# gemini.net
KiCad netlist of a schematic drawn in EAGLE
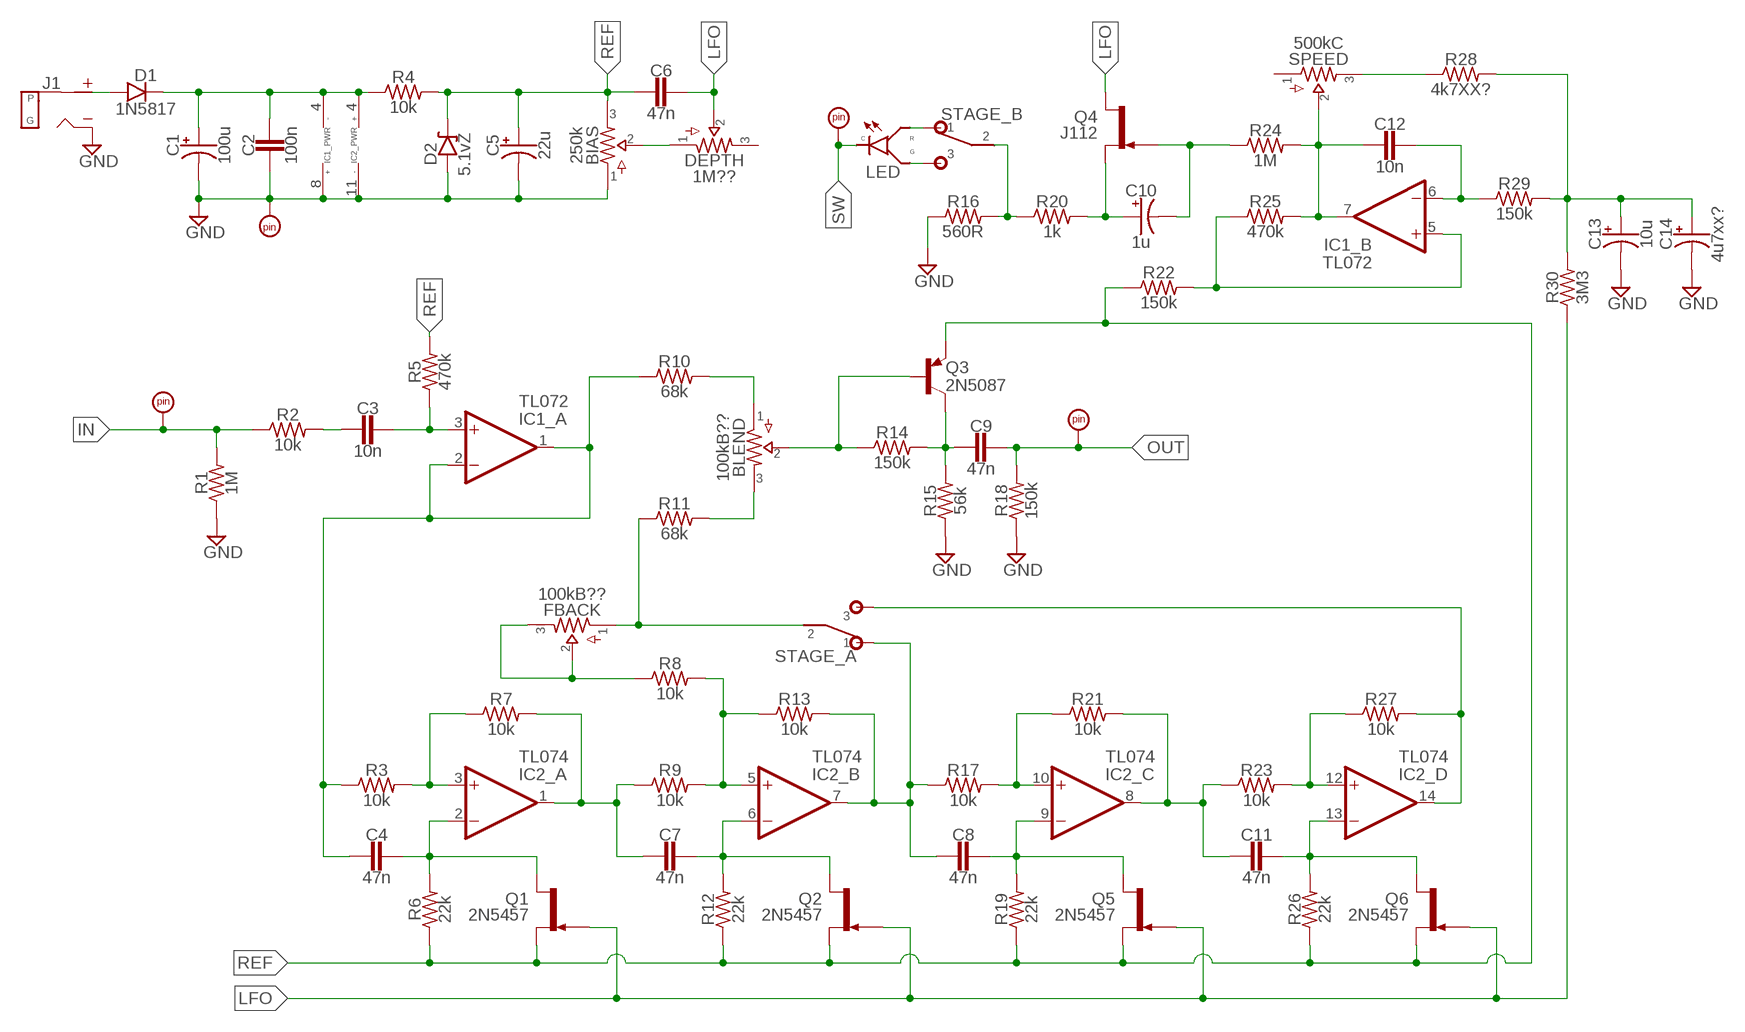
[diagram p0: schematic, sheet 1]

(export (version "E")
  (design (tool "Eeschema 10.0.6"))
  (components
    (comp (ref "BIAS")
      (value "250k")
      (footprint "eagle-import:2262_TRIM")
      (libsource (lib "eagle-import") (part "POTSTRIM"))
    )
    (comp (ref "BLEND")
      (value "100kB??")
      (footprint "eagle-import:16MM")
      (libsource (lib "eagle-import") (part "POTS16MM"))
    )
    (comp (ref "C1")
      (value "100u")
      (footprint "eagle-import:050_020_1")
      (libsource (lib "eagle-import") (part "0501"))
    )
    (comp (ref "C2")
      (value "100n")
      (footprint "eagle-import:050X030_025_2")
      (libsource (lib "eagle-import") (part "CER/FILM2"))
    )
    (comp (ref "C3")
      (value "10n")
      (footprint "eagle-import:050X030_025_2")
      (libsource (lib "eagle-import") (part "CER/FILM2"))
    )
    (comp (ref "C4")
      (value "47n")
      (footprint "eagle-import:050X030_025_2")
      (libsource (lib "eagle-import") (part "CER/FILM2"))
    )
    (comp (ref "C5")
      (value "22u")
      (footprint "eagle-import:050_020_1")
      (libsource (lib "eagle-import") (part "0501"))
    )
    (comp (ref "C6")
      (value "47n")
      (footprint "eagle-import:050X030_025_2")
      (libsource (lib "eagle-import") (part "CER/FILM2"))
    )
    (comp (ref "C7")
      (value "47n")
      (footprint "eagle-import:050X030_025_2")
      (libsource (lib "eagle-import") (part "CER/FILM2"))
    )
    (comp (ref "C8")
      (value "47n")
      (footprint "eagle-import:050X030_025_2")
      (libsource (lib "eagle-import") (part "CER/FILM2"))
    )
    (comp (ref "C9")
      (value "47n")
      (footprint "eagle-import:050X030_025_2")
      (libsource (lib "eagle-import") (part "CER/FILM2"))
    )
    (comp (ref "C10")
      (value "1u")
      (footprint "eagle-import:050_020_1")
      (libsource (lib "eagle-import") (part "0501"))
    )
    (comp (ref "C11")
      (value "47n")
      (footprint "eagle-import:050X030_025_2")
      (libsource (lib "eagle-import") (part "CER/FILM2"))
    )
    (comp (ref "C12")
      (value "10n")
      (footprint "eagle-import:050X030_025_2")
      (libsource (lib "eagle-import") (part "CER/FILM2"))
    )
    (comp (ref "C13")
      (value "10u")
      (footprint "eagle-import:050_020_1")
      (libsource (lib "eagle-import") (part "0501"))
    )
    (comp (ref "C14")
      (value "4u7xx?")
      (footprint "eagle-import:050_020_1")
      (libsource (lib "eagle-import") (part "0501"))
    )
    (comp (ref "D1")
      (value "1N5817")
      (footprint "eagle-import:DO41-2")
      (libsource (lib "eagle-import") (part "DO41.2"))
    )
    (comp (ref "D2")
      (value "5.1vZ")
      (footprint "eagle-import:DO41-3")
      (libsource (lib "eagle-import") (part "ZENER.3"))
    )
    (comp (ref "DEPTH")
      (value "1M??")
      (footprint "eagle-import:16MM")
      (libsource (lib "eagle-import") (part "POTS16MM"))
    )
    (comp (ref "FBACK")
      (value "100kB??")
      (footprint "eagle-import:16MM")
      (libsource (lib "eagle-import") (part "POTS16MM"))
    )
    (comp (ref "IC1")
      (value "TL072")
      (footprint "eagle-import:DIL08")
      (libsource (lib "eagle-import") (part "DUALTH"))
    )
    (comp (ref "IC2")
      (value "TL074")
      (footprint "eagle-import:DIL14")
      (libsource (lib "eagle-import") (part "QUADTH"))
    )
    (comp (ref "J1")
      (value "DC_MONO")
      (footprint "eagle-import:DC")
      (libsource (lib "eagle-import") (part "DC_MONO"))
    )
    (comp (ref "LED")
      (value "LED_DUAL")
      (footprint "eagle-import:LED_DUAL")
      (libsource (lib "eagle-import") (part "LED_DUAL"))
    )
    (comp (ref "PAD1")
      (value "PADSQR")
      (footprint "eagle-import:SQUARE")
      (libsource (lib "eagle-import") (part "PADSQR"))
    )
    (comp (ref "PAD2")
      (value "PADRND")
      (footprint "eagle-import:ROUND")
      (libsource (lib "eagle-import") (part "PADRND"))
    )
    (comp (ref "PAD3")
      (value "PADRND")
      (footprint "eagle-import:ROUND")
      (libsource (lib "eagle-import") (part "PADRND"))
    )
    (comp (ref "PAD4")
      (value "PADSQR")
      (footprint "eagle-import:SQUARE")
      (libsource (lib "eagle-import") (part "PADSQR"))
    )
    (comp (ref "Q1")
      (value "2N5457")
      (footprint "eagle-import:TO92-")
      (libsource (lib "eagle-import") (part "2N5457"))
    )
    (comp (ref "Q2")
      (value "2N5457")
      (footprint "eagle-import:TO92-")
      (libsource (lib "eagle-import") (part "2N5457"))
    )
    (comp (ref "Q3")
      (value "2N5087")
      (footprint "eagle-import:TO92-")
      (libsource (lib "eagle-import") (part "2N5087.1"))
    )
    (comp (ref "Q4")
      (value "J112")
      (footprint "eagle-import:TO92-")
      (libsource (lib "eagle-import") (part "J201"))
    )
    (comp (ref "Q5")
      (value "2N5457")
      (footprint "eagle-import:TO92-")
      (libsource (lib "eagle-import") (part "2N5457"))
    )
    (comp (ref "Q6")
      (value "2N5457")
      (footprint "eagle-import:TO92-")
      (libsource (lib "eagle-import") (part "2N5457"))
    )
    (comp (ref "R1")
      (value "1M")
      (footprint "eagle-import:R0207_3")
      (libsource (lib "eagle-import") (part "R_.3B"))
    )
    (comp (ref "R2")
      (value "10k")
      (footprint "eagle-import:R0207_3")
      (libsource (lib "eagle-import") (part "R_.3B"))
    )
    (comp (ref "R3")
      (value "10k")
      (footprint "eagle-import:R0207_3")
      (libsource (lib "eagle-import") (part "R_.3B"))
    )
    (comp (ref "R4")
      (value "10k")
      (footprint "eagle-import:R0207_3")
      (libsource (lib "eagle-import") (part "R_.3B"))
    )
    (comp (ref "R5")
      (value "470k")
      (footprint "eagle-import:R0207_3")
      (libsource (lib "eagle-import") (part "R_.3B"))
    )
    (comp (ref "R6")
      (value "22k")
      (footprint "eagle-import:R0207_3")
      (libsource (lib "eagle-import") (part "R_.3B"))
    )
    (comp (ref "R7")
      (value "10k")
      (footprint "eagle-import:R0207_3")
      (libsource (lib "eagle-import") (part "R_.3B"))
    )
    (comp (ref "R8")
      (value "10k")
      (footprint "eagle-import:R0207_3")
      (libsource (lib "eagle-import") (part "R_.3B"))
    )
    (comp (ref "R9")
      (value "10k")
      (footprint "eagle-import:R0207_3")
      (libsource (lib "eagle-import") (part "R_.3B"))
    )
    (comp (ref "R10")
      (value "68k")
      (footprint "eagle-import:R0207_3")
      (libsource (lib "eagle-import") (part "R_.3B"))
    )
    (comp (ref "R11")
      (value "68k")
      (footprint "eagle-import:R0207_3")
      (libsource (lib "eagle-import") (part "R_.3B"))
    )
    (comp (ref "R12")
      (value "22k")
      (footprint "eagle-import:R0207_3")
      (libsource (lib "eagle-import") (part "R_.3B"))
    )
    (comp (ref "R13")
      (value "10k")
      (footprint "eagle-import:R0207_3")
      (libsource (lib "eagle-import") (part "R_.3B"))
    )
    (comp (ref "R14")
      (value "150k")
      (footprint "eagle-import:R0207_3")
      (libsource (lib "eagle-import") (part "R_.3B"))
    )
    (comp (ref "R15")
      (value "56k")
      (footprint "eagle-import:R0207_3")
      (libsource (lib "eagle-import") (part "R_.3B"))
    )
    (comp (ref "R16")
      (value "560R")
      (footprint "eagle-import:R0207_3")
      (libsource (lib "eagle-import") (part "R_.3B"))
    )
    (comp (ref "R17")
      (value "10k")
      (footprint "eagle-import:R0207_3")
      (libsource (lib "eagle-import") (part "R_.3B"))
    )
    (comp (ref "R18")
      (value "150k")
      (footprint "eagle-import:R0207_3")
      (libsource (lib "eagle-import") (part "R_.3B"))
    )
    (comp (ref "R19")
      (value "22k")
      (footprint "eagle-import:R0207_3")
      (libsource (lib "eagle-import") (part "R_.3B"))
    )
    (comp (ref "R20")
      (value "1k")
      (footprint "eagle-import:R0207_3")
      (libsource (lib "eagle-import") (part "R_.3B"))
    )
    (comp (ref "R21")
      (value "10k")
      (footprint "eagle-import:R0207_3")
      (libsource (lib "eagle-import") (part "R_.3B"))
    )
    (comp (ref "R22")
      (value "150k")
      (footprint "eagle-import:R0207_3")
      (libsource (lib "eagle-import") (part "R_.3B"))
    )
    (comp (ref "R23")
      (value "10k")
      (footprint "eagle-import:R0207_3")
      (libsource (lib "eagle-import") (part "R_.3B"))
    )
    (comp (ref "R24")
      (value "1M")
      (footprint "eagle-import:R0207_3")
      (libsource (lib "eagle-import") (part "R_.3B"))
    )
    (comp (ref "R25")
      (value "470k")
      (footprint "eagle-import:R0207_3")
      (libsource (lib "eagle-import") (part "R_.3B"))
    )
    (comp (ref "R26")
      (value "22k")
      (footprint "eagle-import:R0207_3")
      (libsource (lib "eagle-import") (part "R_.3B"))
    )
    (comp (ref "R27")
      (value "10k")
      (footprint "eagle-import:R0207_3")
      (libsource (lib "eagle-import") (part "R_.3B"))
    )
    (comp (ref "R28")
      (value "4k7XX?")
      (footprint "eagle-import:R0207_3")
      (libsource (lib "eagle-import") (part "R_.3B"))
    )
    (comp (ref "R29")
      (value "150k")
      (footprint "eagle-import:R0207_3")
      (libsource (lib "eagle-import") (part "R_.3B"))
    )
    (comp (ref "R30")
      (value "3M3")
      (footprint "eagle-import:R0207_3")
      (libsource (lib "eagle-import") (part "R_.3B"))
    )
    (comp (ref "SPEED")
      (value "500kC")
      (footprint "eagle-import:16MM")
      (libsource (lib "eagle-import") (part "POTS16MM"))
    )
    (comp (ref "STAGE")
      (value "DPDTPCB")
      (footprint "eagle-import:DPDT2_PCB")
      (libsource (lib "eagle-import") (part "DPDTPCB"))
    )
  )
  (nets
    (net (code "1") (name "GND") (class "Default")
      (node (ref "BIAS") (pin "1") (pinfunction "1_1") (pintype "passive"))
      (node (ref "C1") (pin "-") (pinfunction "-_-") (pintype "passive"))
      (node (ref "C13") (pin "-") (pinfunction "-_-") (pintype "passive"))
      (node (ref "C14") (pin "-") (pinfunction "-_-") (pintype "passive"))
      (node (ref "C2") (pin "2") (pinfunction "2_2") (pintype "passive"))
      (node (ref "C5") (pin "-") (pinfunction "-_-") (pintype "passive"))
      (node (ref "D2") (pin "A") (pinfunction "A_A") (pintype "passive"))
      (node (ref "IC1") (pin "8") (pinfunction "V+_8") (pintype "power_in"))
      (node (ref "IC2") (pin "11") (pinfunction "V-_11") (pintype "power_in"))
      (node (ref "J1") (pin "S") (pinfunction "SLEEVE_S") (pintype "passive"))
      (node (ref "PAD2") (pin "1") (pinfunction "P$1_1") (pintype "bidirectional"))
      (node (ref "R1") (pin "1") (pinfunction "1_1") (pintype "passive"))
      (node (ref "R15") (pin "1") (pinfunction "1_1") (pintype "passive"))
      (node (ref "R16") (pin "1") (pinfunction "1_1") (pintype "passive"))
      (node (ref "R18") (pin "1") (pinfunction "1_1") (pintype "passive"))
    )
    (net (code "2") (name "IN") (class "Default")
      (node (ref "PAD1") (pin "1") (pinfunction "P$1_1") (pintype "bidirectional"))
      (node (ref "R1") (pin "2") (pinfunction "2_2") (pintype "passive"))
      (node (ref "R2") (pin "1") (pinfunction "1_1") (pintype "passive"))
    )
    (net (code "3") (name "LFO") (class "Default")
      (node (ref "C6") (pin "1") (pinfunction "1_1") (pintype "passive"))
      (node (ref "DEPTH") (pin "2") (pinfunction "2_2") (pintype "passive"))
      (node (ref "Q1") (pin "1") (pinfunction "G_1") (pintype "passive"))
      (node (ref "Q2") (pin "1") (pinfunction "G_1") (pintype "passive"))
      (node (ref "Q4") (pin "3") (pinfunction "D_3") (pintype "passive"))
      (node (ref "Q5") (pin "1") (pinfunction "G_1") (pintype "passive"))
      (node (ref "Q6") (pin "1") (pinfunction "G_1") (pintype "passive"))
      (node (ref "R30") (pin "1") (pinfunction "1_1") (pintype "passive"))
    )
    (net (code "4") (name "Net-(BIAS-Pad2)") (class "Default")
      (node (ref "BIAS") (pin "2") (pinfunction "2_2") (pintype "passive"))
      (node (ref "DEPTH") (pin "1") (pinfunction "1_1") (pintype "passive"))
    )
    (net (code "5") (name "Net-(BLEND-Pad1)") (class "Default")
      (node (ref "BLEND") (pin "1") (pinfunction "1_1") (pintype "passive"))
      (node (ref "R10") (pin "2") (pinfunction "2_2") (pintype "passive"))
    )
    (net (code "6") (name "Net-(BLEND-Pad3)") (class "Default")
      (node (ref "BLEND") (pin "3") (pinfunction "3_3") (pintype "passive"))
      (node (ref "R11") (pin "2") (pinfunction "2_2") (pintype "passive"))
    )
    (net (code "7") (name "Net-(C3-Pad2)") (class "Default")
      (node (ref "C3") (pin "2") (pinfunction "2_2") (pintype "passive"))
      (node (ref "R2") (pin "2") (pinfunction "2_2") (pintype "passive"))
    )
    (net (code "8") (name "Net-(C13-Pad+)") (class "Default")
      (node (ref "C13") (pin "+") (pinfunction "+_+") (pintype "passive"))
      (node (ref "C14") (pin "+") (pinfunction "+_+") (pintype "passive"))
      (node (ref "R28") (pin "2") (pinfunction "2_2") (pintype "passive"))
      (node (ref "R29") (pin "2") (pinfunction "2_2") (pintype "passive"))
      (node (ref "R30") (pin "2") (pinfunction "2_2") (pintype "passive"))
    )
    (net (code "9") (name "Net-(FBACK-Pad2)") (class "Default")
      (node (ref "FBACK") (pin "2") (pinfunction "2_2") (pintype "passive"))
      (node (ref "FBACK") (pin "3") (pinfunction "3_3") (pintype "passive"))
      (node (ref "R8") (pin "1") (pinfunction "1_1") (pintype "passive"))
    )
    (net (code "10") (name "Net-(IC1A-+IN)") (class "Default")
      (node (ref "C3") (pin "1") (pinfunction "1_1") (pintype "passive"))
      (node (ref "IC1") (pin "3") (pinfunction "+IN_3") (pintype "input"))
      (node (ref "R5") (pin "1") (pinfunction "1_1") (pintype "passive"))
    )
    (net (code "11") (name "Net-(IC1A--IN)") (class "Default")
      (node (ref "C4") (pin "2") (pinfunction "2_2") (pintype "passive"))
      (node (ref "IC1") (pin "1") (pinfunction "OUT_1") (pintype "output"))
      (node (ref "IC1") (pin "2") (pinfunction "-IN_2") (pintype "input"))
      (node (ref "R10") (pin "1") (pinfunction "1_1") (pintype "passive"))
      (node (ref "R3") (pin "1") (pinfunction "1_1") (pintype "passive"))
    )
    (net (code "12") (name "Net-(IC1B-+IN)") (class "Default")
      (node (ref "IC1") (pin "5") (pinfunction "+IN_5") (pintype "input"))
      (node (ref "R22") (pin "2") (pinfunction "2_2") (pintype "passive"))
      (node (ref "R25") (pin "1") (pinfunction "1_1") (pintype "passive"))
    )
    (net (code "13") (name "Net-(IC1B--IN)") (class "Default")
      (node (ref "C12") (pin "1") (pinfunction "1_1") (pintype "passive"))
      (node (ref "IC1") (pin "6") (pinfunction "-IN_6") (pintype "input"))
      (node (ref "R29") (pin "1") (pinfunction "1_1") (pintype "passive"))
    )
    (net (code "14") (name "Net-(IC1B-OUT)") (class "Default")
      (node (ref "C12") (pin "2") (pinfunction "2_2") (pintype "passive"))
      (node (ref "IC1") (pin "7") (pinfunction "OUT_7") (pintype "output"))
      (node (ref "R24") (pin "2") (pinfunction "2_2") (pintype "passive"))
      (node (ref "R25") (pin "2") (pinfunction "2_2") (pintype "passive"))
      (node (ref "SPEED") (pin "2") (pinfunction "2_2") (pintype "passive"))
    )
    (net (code "15") (name "Net-(IC1C-V-)") (class "Default")
      (node (ref "C1") (pin "+") (pinfunction "+_+") (pintype "passive"))
      (node (ref "C2") (pin "1") (pinfunction "1_1") (pintype "passive"))
      (node (ref "D1") (pin "C") (pinfunction "C_C") (pintype "passive"))
      (node (ref "IC1") (pin "4") (pinfunction "V-_4") (pintype "power_in"))
      (node (ref "IC2") (pin "4") (pinfunction "V+_4") (pintype "power_in"))
      (node (ref "R4") (pin "1") (pinfunction "1_1") (pintype "passive"))
    )
    (net (code "16") (name "Net-(IC2A-+IN)") (class "Default")
      (node (ref "IC2") (pin "3") (pinfunction "+IN_3") (pintype "input"))
      (node (ref "R3") (pin "2") (pinfunction "2_2") (pintype "passive"))
      (node (ref "R7") (pin "1") (pinfunction "1_1") (pintype "passive"))
    )
    (net (code "17") (name "Net-(IC2A--IN)") (class "Default")
      (node (ref "C4") (pin "1") (pinfunction "1_1") (pintype "passive"))
      (node (ref "IC2") (pin "2") (pinfunction "-IN_2") (pintype "input"))
      (node (ref "Q1") (pin "3") (pinfunction "D_3") (pintype "passive"))
      (node (ref "R6") (pin "2") (pinfunction "2_2") (pintype "passive"))
    )
    (net (code "18") (name "Net-(IC2A-OUT)") (class "Default")
      (node (ref "C7") (pin "2") (pinfunction "2_2") (pintype "passive"))
      (node (ref "IC2") (pin "1") (pinfunction "OUT_1") (pintype "output"))
      (node (ref "R7") (pin "2") (pinfunction "2_2") (pintype "passive"))
      (node (ref "R9") (pin "1") (pinfunction "1_1") (pintype "passive"))
    )
    (net (code "19") (name "Net-(IC2B-+IN)") (class "Default")
      (node (ref "IC2") (pin "5") (pinfunction "+IN_5") (pintype "input"))
      (node (ref "R13") (pin "1") (pinfunction "1_1") (pintype "passive"))
      (node (ref "R8") (pin "2") (pinfunction "2_2") (pintype "passive"))
      (node (ref "R9") (pin "2") (pinfunction "2_2") (pintype "passive"))
    )
    (net (code "20") (name "Net-(IC2B--IN)") (class "Default")
      (node (ref "C7") (pin "1") (pinfunction "1_1") (pintype "passive"))
      (node (ref "IC2") (pin "6") (pinfunction "-IN_6") (pintype "input"))
      (node (ref "Q2") (pin "3") (pinfunction "D_3") (pintype "passive"))
      (node (ref "R12") (pin "2") (pinfunction "2_2") (pintype "passive"))
    )
    (net (code "21") (name "Net-(IC2B-OUT)") (class "Default")
      (node (ref "C8") (pin "2") (pinfunction "2_2") (pintype "passive"))
      (node (ref "IC2") (pin "7") (pinfunction "OUT_7") (pintype "output"))
      (node (ref "R13") (pin "2") (pinfunction "2_2") (pintype "passive"))
      (node (ref "R17") (pin "1") (pinfunction "1_1") (pintype "passive"))
      (node (ref "STAGE") (pin "A1") (pinfunction "1_A1") (pintype "passive"))
    )
    (net (code "22") (name "Net-(IC2C-+IN)") (class "Default")
      (node (ref "IC2") (pin "10") (pinfunction "+IN_10") (pintype "input"))
      (node (ref "R17") (pin "2") (pinfunction "2_2") (pintype "passive"))
      (node (ref "R21") (pin "1") (pinfunction "1_1") (pintype "passive"))
    )
    (net (code "23") (name "Net-(IC2C--IN)") (class "Default")
      (node (ref "C8") (pin "1") (pinfunction "1_1") (pintype "passive"))
      (node (ref "IC2") (pin "9") (pinfunction "-IN_9") (pintype "input"))
      (node (ref "Q5") (pin "3") (pinfunction "D_3") (pintype "passive"))
      (node (ref "R19") (pin "2") (pinfunction "2_2") (pintype "passive"))
    )
    (net (code "24") (name "Net-(IC2C-OUT)") (class "Default")
      (node (ref "C11") (pin "2") (pinfunction "2_2") (pintype "passive"))
      (node (ref "IC2") (pin "8") (pinfunction "OUT_8") (pintype "output"))
      (node (ref "R21") (pin "2") (pinfunction "2_2") (pintype "passive"))
      (node (ref "R23") (pin "1") (pinfunction "1_1") (pintype "passive"))
    )
    (net (code "25") (name "Net-(IC2D-+IN)") (class "Default")
      (node (ref "IC2") (pin "12") (pinfunction "+IN_12") (pintype "input"))
      (node (ref "R23") (pin "2") (pinfunction "2_2") (pintype "passive"))
      (node (ref "R27") (pin "1") (pinfunction "1_1") (pintype "passive"))
    )
    (net (code "26") (name "Net-(IC2D--IN)") (class "Default")
      (node (ref "C11") (pin "1") (pinfunction "1_1") (pintype "passive"))
      (node (ref "IC2") (pin "13") (pinfunction "-IN_13") (pintype "input"))
      (node (ref "Q6") (pin "3") (pinfunction "D_3") (pintype "passive"))
      (node (ref "R26") (pin "2") (pinfunction "2_2") (pintype "passive"))
    )
    (net (code "27") (name "Net-(IC2D-OUT)") (class "Default")
      (node (ref "IC2") (pin "14") (pinfunction "OUT_14") (pintype "output"))
      (node (ref "R27") (pin "2") (pinfunction "2_2") (pintype "passive"))
      (node (ref "STAGE") (pin "A3") (pinfunction "3_A3") (pintype "passive"))
    )
    (net (code "28") (name "Net-(J1-TIP)") (class "Default")
      (node (ref "D1") (pin "A") (pinfunction "A_A") (pintype "passive"))
      (node (ref "J1") (pin "T") (pinfunction "TIP_T") (pintype "passive"))
    )
    (net (code "29") (name "Net-(Q3-B)") (class "Default")
      (node (ref "BLEND") (pin "2") (pinfunction "2_2") (pintype "passive"))
      (node (ref "Q3") (pin "2") (pinfunction "B_2") (pintype "passive"))
      (node (ref "R14") (pin "1") (pinfunction "1_1") (pintype "passive"))
    )
    (net (code "30") (name "Net-(Q3-C)") (class "Default")
      (node (ref "C9") (pin "2") (pinfunction "2_2") (pintype "passive"))
      (node (ref "Q3") (pin "1") (pinfunction "C_1") (pintype "passive"))
      (node (ref "R14") (pin "2") (pinfunction "2_2") (pintype "passive"))
      (node (ref "R15") (pin "2") (pinfunction "2_2") (pintype "passive"))
    )
    (net (code "31") (name "Net-(Q4-G)") (class "Default")
      (node (ref "C10") (pin "-") (pinfunction "-_-") (pintype "passive"))
      (node (ref "Q4") (pin "1") (pinfunction "G_1") (pintype "passive"))
      (node (ref "R24") (pin "1") (pinfunction "1_1") (pintype "passive"))
    )
    (net (code "32") (name "Net-(Q4-S)") (class "Default")
      (node (ref "C10") (pin "+") (pinfunction "+_+") (pintype "passive"))
      (node (ref "Q4") (pin "2") (pinfunction "S_2") (pintype "passive"))
      (node (ref "R20") (pin "2") (pinfunction "2_2") (pintype "passive"))
    )
    (net (code "33") (name "Net-(R28-Pad1)") (class "Default")
      (node (ref "R28") (pin "1") (pinfunction "1_1") (pintype "passive"))
      (node (ref "SPEED") (pin "3") (pinfunction "3_3") (pintype "passive"))
    )
    (net (code "34") (name "Net-(STAGEA-2)") (class "Default")
      (node (ref "FBACK") (pin "1") (pinfunction "1_1") (pintype "passive"))
      (node (ref "R11") (pin "1") (pinfunction "1_1") (pintype "passive"))
      (node (ref "STAGE") (pin "A2") (pinfunction "2_A2") (pintype "passive"))
    )
    (net (code "35") (name "Net-(STAGEB-1)") (class "Default")
      (node (ref "LED") (pin "R") (pinfunction "R_R") (pintype "bidirectional"))
      (node (ref "STAGE") (pin "B1") (pinfunction "1_B1") (pintype "passive"))
    )
    (net (code "36") (name "Net-(STAGEB-2)") (class "Default")
      (node (ref "R16") (pin "2") (pinfunction "2_2") (pintype "passive"))
      (node (ref "R20") (pin "1") (pinfunction "1_1") (pintype "passive"))
      (node (ref "STAGE") (pin "B2") (pinfunction "2_B2") (pintype "passive"))
    )
    (net (code "37") (name "Net-(STAGEB-3)") (class "Default")
      (node (ref "LED") (pin "G") (pinfunction "G_G") (pintype "bidirectional"))
      (node (ref "STAGE") (pin "B3") (pinfunction "3_B3") (pintype "passive"))
    )
    (net (code "38") (name "OUT") (class "Default")
      (node (ref "C9") (pin "1") (pinfunction "1_1") (pintype "passive"))
      (node (ref "PAD4") (pin "1") (pinfunction "P$1_1") (pintype "bidirectional"))
      (node (ref "R18") (pin "2") (pinfunction "2_2") (pintype "passive"))
    )
    (net (code "39") (name "REF") (class "Default")
      (node (ref "BIAS") (pin "3") (pinfunction "3_3") (pintype "passive"))
      (node (ref "C5") (pin "+") (pinfunction "+_+") (pintype "passive"))
      (node (ref "C6") (pin "2") (pinfunction "2_2") (pintype "passive"))
      (node (ref "D2") (pin "C") (pinfunction "C_C") (pintype "passive"))
      (node (ref "Q1") (pin "2") (pinfunction "S_2") (pintype "passive"))
      (node (ref "Q2") (pin "2") (pinfunction "S_2") (pintype "passive"))
      (node (ref "Q3") (pin "3") (pinfunction "E_3") (pintype "passive"))
      (node (ref "Q5") (pin "2") (pinfunction "S_2") (pintype "passive"))
      (node (ref "Q6") (pin "2") (pinfunction "S_2") (pintype "passive"))
      (node (ref "R12") (pin "1") (pinfunction "1_1") (pintype "passive"))
      (node (ref "R19") (pin "1") (pinfunction "1_1") (pintype "passive"))
      (node (ref "R22") (pin "1") (pinfunction "1_1") (pintype "passive"))
      (node (ref "R26") (pin "1") (pinfunction "1_1") (pintype "passive"))
      (node (ref "R4") (pin "2") (pinfunction "2_2") (pintype "passive"))
      (node (ref "R5") (pin "2") (pinfunction "2_2") (pintype "passive"))
      (node (ref "R6") (pin "1") (pinfunction "1_1") (pintype "passive"))
    )
    (net (code "40") (name "SW") (class "Default")
      (node (ref "LED") (pin "C") (pinfunction "C_C") (pintype "bidirectional"))
      (node (ref "PAD3") (pin "1") (pinfunction "P$1_1") (pintype "bidirectional"))
    )
    (net (code "41") (name "unconnected-(DEPTH-Pad3)") (class "Default")
      (node (ref "DEPTH") (pin "3") (pinfunction "3_3") (pintype "passive"))
    )
    (net (code "42") (name "unconnected-(SPEED-Pad1)") (class "Default")
      (node (ref "SPEED") (pin "1") (pinfunction "1_1") (pintype "passive"))
    )
  )
)
